# Microcontroller.net
KiCad netlist of a schematic drawn in Altium Designer
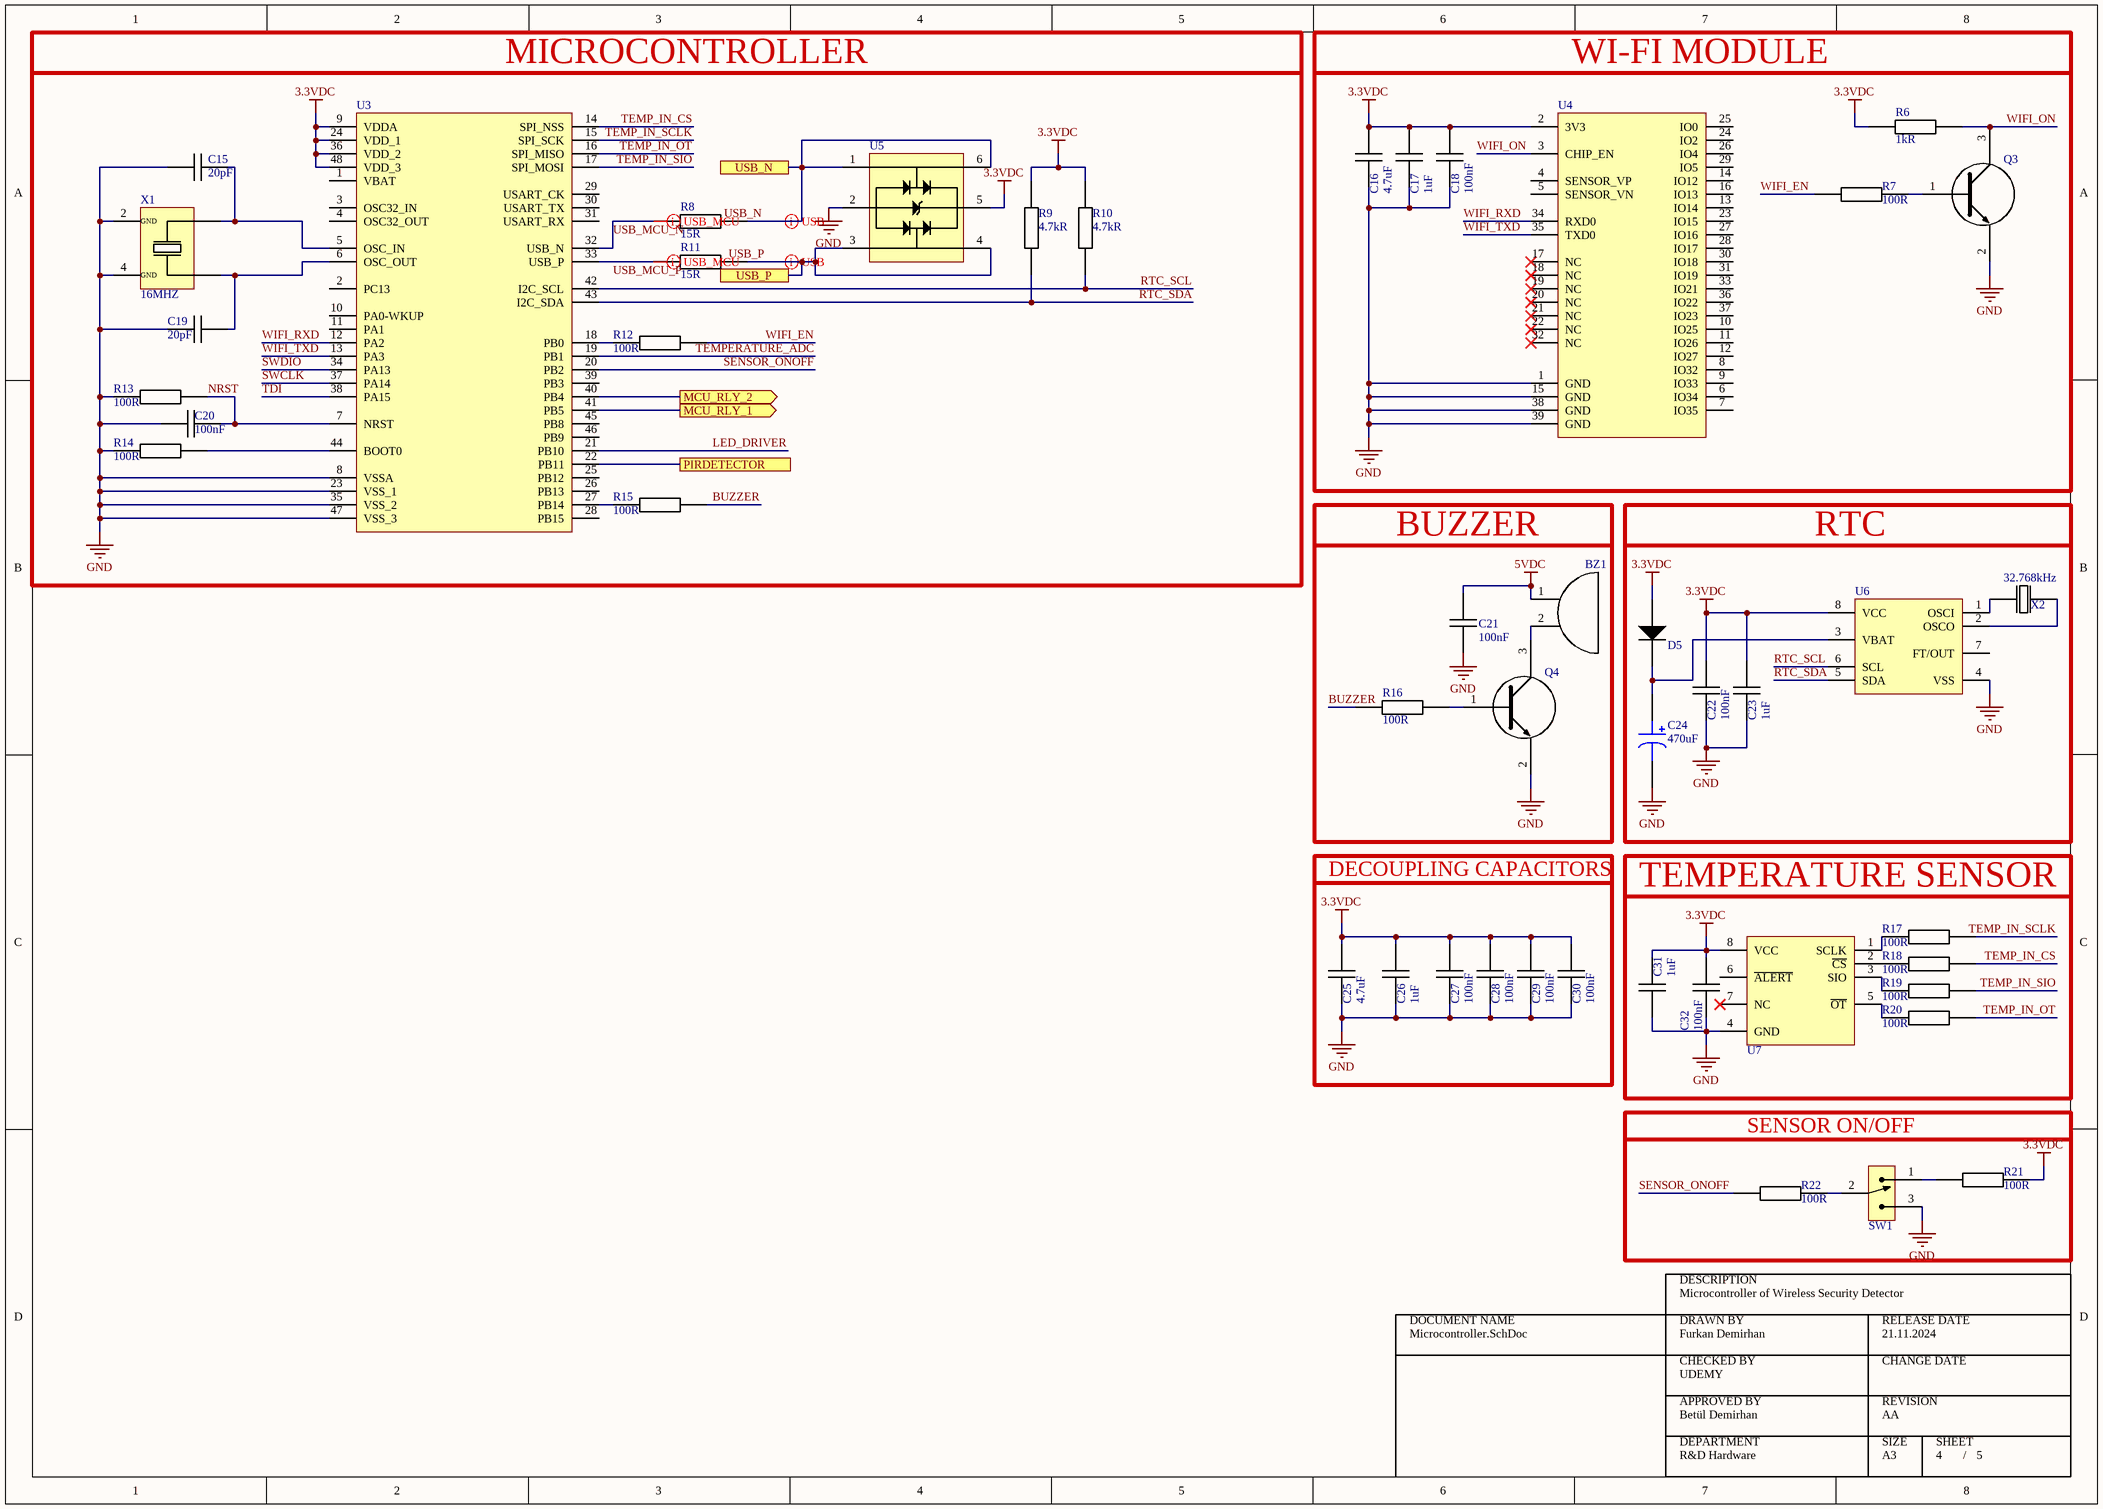
[diagram p0: Microcontroller.SchDoc]

(export (version "E")
  (design (tool "Eeschema 10.0.6"))
  (components
    (comp (ref "BZ1")
      (value "CMI-9605IC-0580T")
      (footprint "CMI-9605IC-0580T")
      (description "Audio Buzzer Magnetic 3VDC 7VDC 30mA 5VDC 85dB 2600Hz to 2800Hz Through Hole Pin Box")
      (fields (field (name "MANUFACTURER") "CUI Devices") (field (name "DESIGNED BY") "FURKAN"))
      (libsource (lib "Udemy_Library") (part "CMI-9605IC-0580T"))
    )
    (comp (ref "C15")
      (value "20pF")
      (footprint "CAP_0603")
      (description "CAP CER 20pF ±5% 0603 SMD")
      (fields
        (field (name "MANUFACTURER") "Samsung")
        (field (name "MANUFACTURER PART NUMBER") "CL10C200JB8NNNC")
        (field (name "DESIGNED BY") "FURKAN")
      )
      (libsource (lib "Udemy_Library") (part "CAP CER 20pF 0603"))
    )
    (comp (ref "C16")
      (value "4.7uF")
      (footprint "CAP_0805")
      (description "Multilayer Ceramic Capacitor, 4.7 uF, 25 V, ± 10%, X5R, 0805 [2012 Metric]")
      (fields
        (field (name "MANUFACTURER") "Samsung")
        (field (name "MANUFACTURER PART NUMBER") "CL21A475KAQNNNE")
        (field (name "DESIGNED BY") "FURKAN")
      )
      (libsource (lib "Udemy_Library") (part "CAP CER 4.7uF 0805"))
    )
    (comp (ref "C17")
      (value "1uF")
      (footprint "CAP_0805")
      (description "Multilayer Ceramic Capacitor, 1 uF, 50 V, 10%, X7R, 0805 [2012 Metric]")
      (fields
        (field (name "MANUFACTURER") "Samsung")
        (field (name "MANUFACTURER PART NUMBER") "CL21B105KBFNNNE")
        (field (name "DESIGNED BY") "FURKAN")
      )
      (libsource (lib "Udemy_Library") (part "CAP CER 1uF 0805"))
    )
    (comp (ref "C18")
      (value "100nF")
      (footprint "CAP_0805")
      (description "CAP CER 100 nF 10% 50 V 0805 SMD")
      (fields
        (field (name "MANUFACTURER") "Samsung")
        (field (name "MANUFACTURER PART NUMBER") "CL21B104KBCNNNC")
        (field (name "DESIGNED BY") "FURKAN")
      )
      (libsource (lib "Udemy_Library") (part "CAP CER 100nF 0805"))
    )
    (comp (ref "C19")
      (value "20pF")
      (footprint "CAP_0603")
      (description "CAP CER 20pF ±5% 0603 SMD")
      (fields
        (field (name "MANUFACTURER") "Samsung")
        (field (name "MANUFACTURER PART NUMBER") "CL10C200JB8NNNC")
        (field (name "DESIGNED BY") "FURKAN")
      )
      (libsource (lib "Udemy_Library") (part "CAP CER 20pF 0603"))
    )
    (comp (ref "C20")
      (value "100nF")
      (footprint "CAP_0805")
      (description "CAP CER 100 nF 10% 50 V 0805 SMD")
      (fields
        (field (name "MANUFACTURER") "Samsung")
        (field (name "MANUFACTURER PART NUMBER") "CL21B104KBCNNNC")
        (field (name "DESIGNED BY") "FURKAN")
      )
      (libsource (lib "Udemy_Library") (part "CAP CER 100nF 0805"))
    )
    (comp (ref "C21")
      (value "100nF")
      (footprint "CAP_0805")
      (description "CAP CER 100 nF 10% 50 V 0805 SMD")
      (fields
        (field (name "MANUFACTURER") "Samsung")
        (field (name "MANUFACTURER PART NUMBER") "CL21B104KBCNNNC")
        (field (name "DESIGNED BY") "FURKAN")
      )
      (libsource (lib "Udemy_Library") (part "CAP CER 100nF 0805"))
    )
    (comp (ref "C22")
      (value "100nF")
      (footprint "CAP_0805")
      (description "CAP CER 100 nF 10% 50 V 0805 SMD")
      (fields
        (field (name "MANUFACTURER") "Samsung")
        (field (name "MANUFACTURER PART NUMBER") "CL21B104KBCNNNC")
        (field (name "DESIGNED BY") "FURKAN")
      )
      (libsource (lib "Udemy_Library") (part "CAP CER 100nF 0805"))
    )
    (comp (ref "C23")
      (value "1uF")
      (footprint "CAP_0805")
      (description "Multilayer Ceramic Capacitor, 1 uF, 50 V, 10%, X7R, 0805 [2012 Metric]")
      (fields
        (field (name "MANUFACTURER") "Samsung")
        (field (name "MANUFACTURER PART NUMBER") "CL21B105KBFNNNE")
        (field (name "DESIGNED BY") "FURKAN")
      )
      (libsource (lib "Udemy_Library") (part "CAP CER 1uF 0805"))
    )
    (comp (ref "C24")
      (value "ESH477M050AH4AA")
      (footprint "CAP_RADIAL_R10_P5")
      (description "Electrolytic capacitor, 470 µF, 50 V (DC), ±20 %, radial, pitch 5 mm, Ø 13 mm")
      (fields
        (field (name "MANUFACTURER") "KEMET")
        (field (name "CAPACITANCE") "470uF")
        (field (name "DESIGNED BY") "FURKAN")
      )
      (libsource (lib "Udemy_Library") (part "CAP ALU ELEC 470uF"))
    )
    (comp (ref "C25")
      (value "4.7uF")
      (footprint "CAP_0805")
      (description "Multilayer Ceramic Capacitor, 4.7 uF, 25 V, ± 10%, X5R, 0805 [2012 Metric]")
      (fields
        (field (name "MANUFACTURER") "Samsung")
        (field (name "MANUFACTURER PART NUMBER") "CL21A475KAQNNNE")
        (field (name "DESIGNED BY") "FURKAN")
      )
      (libsource (lib "Udemy_Library") (part "CAP CER 4.7uF 0805"))
    )
    (comp (ref "C26")
      (value "1uF")
      (footprint "CAP_0805")
      (description "Multilayer Ceramic Capacitor, 1 uF, 50 V, 10%, X7R, 0805 [2012 Metric]")
      (fields
        (field (name "MANUFACTURER") "Samsung")
        (field (name "MANUFACTURER PART NUMBER") "CL21B105KBFNNNE")
        (field (name "DESIGNED BY") "FURKAN")
      )
      (libsource (lib "Udemy_Library") (part "CAP CER 1uF 0805"))
    )
    (comp (ref "C27")
      (value "100nF")
      (footprint "CAP_0805")
      (description "CAP CER 100 nF 10% 50 V 0805 SMD")
      (fields
        (field (name "MANUFACTURER") "Samsung")
        (field (name "MANUFACTURER PART NUMBER") "CL21B104KBCNNNC")
        (field (name "DESIGNED BY") "FURKAN")
      )
      (libsource (lib "Udemy_Library") (part "CAP CER 100nF 0805"))
    )
    (comp (ref "C28")
      (value "100nF")
      (footprint "CAP_0805")
      (description "CAP CER 100 nF 10% 50 V 0805 SMD")
      (fields
        (field (name "MANUFACTURER") "Samsung")
        (field (name "MANUFACTURER PART NUMBER") "CL21B104KBCNNNC")
        (field (name "DESIGNED BY") "FURKAN")
      )
      (libsource (lib "Udemy_Library") (part "CAP CER 100nF 0805"))
    )
    (comp (ref "C29")
      (value "100nF")
      (footprint "CAP_0805")
      (description "CAP CER 100 nF 10% 50 V 0805 SMD")
      (fields
        (field (name "MANUFACTURER") "Samsung")
        (field (name "MANUFACTURER PART NUMBER") "CL21B104KBCNNNC")
        (field (name "DESIGNED BY") "FURKAN")
      )
      (libsource (lib "Udemy_Library") (part "CAP CER 100nF 0805"))
    )
    (comp (ref "C30")
      (value "100nF")
      (footprint "CAP_0805")
      (description "CAP CER 100 nF 10% 50 V 0805 SMD")
      (fields
        (field (name "MANUFACTURER") "Samsung")
        (field (name "MANUFACTURER PART NUMBER") "CL21B104KBCNNNC")
        (field (name "DESIGNED BY") "FURKAN")
      )
      (libsource (lib "Udemy_Library") (part "CAP CER 100nF 0805"))
    )
    (comp (ref "C31")
      (value "1uF")
      (footprint "CAP_0805")
      (description "Multilayer Ceramic Capacitor, 1 uF, 50 V, 10%, X7R, 0805 [2012 Metric]")
      (fields
        (field (name "MANUFACTURER") "Samsung")
        (field (name "MANUFACTURER PART NUMBER") "CL21B105KBFNNNE")
        (field (name "DESIGNED BY") "FURKAN")
      )
      (libsource (lib "Udemy_Library") (part "CAP CER 1uF 0805"))
    )
    (comp (ref "C32")
      (value "100nF")
      (footprint "CAP_0805")
      (description "CAP CER 100 nF 10% 50 V 0805 SMD")
      (fields
        (field (name "MANUFACTURER") "Samsung")
        (field (name "MANUFACTURER PART NUMBER") "CL21B104KBCNNNC")
        (field (name "DESIGNED BY") "FURKAN")
      )
      (libsource (lib "Udemy_Library") (part "CAP CER 100nF 0805"))
    )
    (comp (ref "D5")
      (value "1N4148WS")
      (footprint "SOD323F")
      (description "Diode Ultra Fast Recovery Rectifier 75V 0.15A 2-Pin SOD-323F T/R")
      (fields
        (field (name "MANUFACTURER") "ON Semiconductor / Fairchild")
        (field (name "DESIGNED BY") "FURKAN")
      )
      (libsource (lib "Udemy_Library") (part "1N4148WS"))
    )
    (comp (ref "Q3")
      (value "MMBT3904-7-F")
      (footprint "SOT23F")
      (description "Transistor General Purpose BJT NPN 40 Volt 0.2A Automotive 3-Pin SOT-23")
      (fields (field (name "MANUFACTURER") "Diodes Zetex") (field (name "DESIGNED BY") "FURKAN"))
      (libsource (lib "Udemy_Library") (part "MMBT3904-7-F"))
    )
    (comp (ref "Q4")
      (value "MMBT3904-7-F")
      (footprint "SOT23F")
      (description "Transistor General Purpose BJT NPN 40 Volt 0.2A Automotive 3-Pin SOT-23")
      (fields (field (name "MANUFACTURER") "Diodes Zetex") (field (name "DESIGNED BY") "FURKAN"))
      (libsource (lib "Udemy_Library") (part "MMBT3904-7-F"))
    )
    (comp (ref "R6")
      (value "1kR")
      (footprint "RES_0603")
      (description "RES 1K OHM 1% 0603 SMD")
      (fields
        (field (name "MANUFACTURER") "Yageo")
        (field (name "MANUFACTURER PART NUMBER") "RC0603FR-071KL")
        (field (name "DESIGNED BY") "FURKAN")
      )
      (libsource (lib "Udemy_Library") (part "RES 1K OHM 0603"))
    )
    (comp (ref "R7")
      (value "100R")
      (footprint "RES_0603")
      (description "RES 100 OHM 1% 0603 SMD")
      (fields
        (field (name "MANUFACTURER") "Yageo")
        (field (name "MANUFACTURER PART NUMBER") "RC0603FR-07100RL")
        (field (name "DESIGNED BY") "FURKAN")
      )
      (libsource (lib "Udemy_Library") (part "RES 100 OHM 0603"))
    )
    (comp (ref "R8")
      (value "15R")
      (footprint "RES_0603")
      (description "RES 15 OHM 5% 0603 SMD")
      (fields
        (field (name "MANUFACTURER") "Yageo")
        (field (name "MANUFACTURER PART NUMBER") "RC0603JR-0715RL")
        (field (name "DESIGNED BY") "FURKAN")
      )
      (libsource (lib "Udemy_Library") (part "RES 15 OHM 0603"))
    )
    (comp (ref "R9")
      (value "4.7kR")
      (footprint "RES_0603")
      (description "RES 4.7K OHM 5% 0603 SMD")
      (fields
        (field (name "MANUFACTURER") "Yageo")
        (field (name "MANUFACTURER PART NUMBER") "RC0603JR-074K7L")
        (field (name "DESIGNED BY") "FURKAN")
      )
      (libsource (lib "Udemy_Library") (part "RES 4.7K OHM 0603"))
    )
    (comp (ref "R10")
      (value "4.7kR")
      (footprint "RES_0603")
      (description "RES 4.7K OHM 5% 0603 SMD")
      (fields
        (field (name "MANUFACTURER") "Yageo")
        (field (name "MANUFACTURER PART NUMBER") "RC0603JR-074K7L")
        (field (name "DESIGNED BY") "FURKAN")
      )
      (libsource (lib "Udemy_Library") (part "RES 4.7K OHM 0603"))
    )
    (comp (ref "R11")
      (value "15R")
      (footprint "RES_0603")
      (description "RES 15 OHM 5% 0603 SMD")
      (fields
        (field (name "MANUFACTURER") "Yageo")
        (field (name "MANUFACTURER PART NUMBER") "RC0603JR-0715RL")
        (field (name "DESIGNED BY") "FURKAN")
      )
      (libsource (lib "Udemy_Library") (part "RES 15 OHM 0603"))
    )
    (comp (ref "R12")
      (value "100R")
      (footprint "RES_0603")
      (description "RES 100 OHM 1% 0603 SMD")
      (fields
        (field (name "MANUFACTURER") "Yageo")
        (field (name "MANUFACTURER PART NUMBER") "RC0603FR-07100RL")
        (field (name "DESIGNED BY") "FURKAN")
      )
      (libsource (lib "Udemy_Library") (part "RES 100 OHM 0603"))
    )
    (comp (ref "R13")
      (value "100R")
      (footprint "RES_0603")
      (description "RES 100 OHM 1% 0603 SMD")
      (fields
        (field (name "MANUFACTURER") "Yageo")
        (field (name "MANUFACTURER PART NUMBER") "RC0603FR-07100RL")
        (field (name "DESIGNED BY") "FURKAN")
      )
      (libsource (lib "Udemy_Library") (part "RES 100 OHM 0603"))
    )
    (comp (ref "R14")
      (value "100R")
      (footprint "RES_0603")
      (description "RES 100 OHM 1% 0603 SMD")
      (fields
        (field (name "MANUFACTURER") "Yageo")
        (field (name "MANUFACTURER PART NUMBER") "RC0603FR-07100RL")
        (field (name "DESIGNED BY") "FURKAN")
      )
      (libsource (lib "Udemy_Library") (part "RES 100 OHM 0603"))
    )
    (comp (ref "R15")
      (value "100R")
      (footprint "RES_0603")
      (description "RES 100 OHM 1% 0603 SMD")
      (fields
        (field (name "MANUFACTURER") "Yageo")
        (field (name "MANUFACTURER PART NUMBER") "RC0603FR-07100RL")
        (field (name "DESIGNED BY") "FURKAN")
      )
      (libsource (lib "Udemy_Library") (part "RES 100 OHM 0603"))
    )
    (comp (ref "R16")
      (value "100R")
      (footprint "RES_0603")
      (description "RES 100 OHM 1% 0603 SMD")
      (fields
        (field (name "MANUFACTURER") "Yageo")
        (field (name "MANUFACTURER PART NUMBER") "RC0603FR-07100RL")
        (field (name "DESIGNED BY") "FURKAN")
      )
      (libsource (lib "Udemy_Library") (part "RES 100 OHM 0603"))
    )
    (comp (ref "R17")
      (value "100R")
      (footprint "RES_0603")
      (description "RES 100 OHM 1% 0603 SMD")
      (fields
        (field (name "MANUFACTURER") "Yageo")
        (field (name "MANUFACTURER PART NUMBER") "RC0603FR-07100RL")
        (field (name "DESIGNED BY") "FURKAN")
      )
      (libsource (lib "Udemy_Library") (part "RES 100 OHM 0603"))
    )
    (comp (ref "R18")
      (value "100R")
      (footprint "RES_0603")
      (description "RES 100 OHM 1% 0603 SMD")
      (fields
        (field (name "MANUFACTURER") "Yageo")
        (field (name "MANUFACTURER PART NUMBER") "RC0603FR-07100RL")
        (field (name "DESIGNED BY") "FURKAN")
      )
      (libsource (lib "Udemy_Library") (part "RES 100 OHM 0603"))
    )
    (comp (ref "R19")
      (value "100R")
      (footprint "RES_0603")
      (description "RES 100 OHM 1% 0603 SMD")
      (fields
        (field (name "MANUFACTURER") "Yageo")
        (field (name "MANUFACTURER PART NUMBER") "RC0603FR-07100RL")
        (field (name "DESIGNED BY") "FURKAN")
      )
      (libsource (lib "Udemy_Library") (part "RES 100 OHM 0603"))
    )
    (comp (ref "R20")
      (value "100R")
      (footprint "RES_0603")
      (description "RES 100 OHM 1% 0603 SMD")
      (fields
        (field (name "MANUFACTURER") "Yageo")
        (field (name "MANUFACTURER PART NUMBER") "RC0603FR-07100RL")
        (field (name "DESIGNED BY") "FURKAN")
      )
      (libsource (lib "Udemy_Library") (part "RES 100 OHM 0603"))
    )
    (comp (ref "R21")
      (value "100R")
      (footprint "RES_0603")
      (description "RES 100 OHM 1% 0603 SMD")
      (fields
        (field (name "MANUFACTURER") "Yageo")
        (field (name "MANUFACTURER PART NUMBER") "RC0603FR-07100RL")
        (field (name "DESIGNED BY") "FURKAN")
      )
      (libsource (lib "Udemy_Library") (part "RES 100 OHM 0603"))
    )
    (comp (ref "R22")
      (value "100R")
      (footprint "RES_0603")
      (description "RES 100 OHM 1% 0603 SMD")
      (fields
        (field (name "MANUFACTURER") "Yageo")
        (field (name "MANUFACTURER PART NUMBER") "RC0603FR-07100RL")
        (field (name "DESIGNED BY") "FURKAN")
      )
      (libsource (lib "Udemy_Library") (part "RES 100 OHM 0603"))
    )
    (comp (ref "SW1")
      (value "EG1215AA")
      (footprint "EG1215AA")
      (description "Slide Switch, SPDT, 0.025A, 24V, SMD")
      (fields (field (name "MANUFACTURER") "E-Switch") (field (name "DESIGNED BY") "FURKAN"))
      (libsource (lib "Udemy_Library") (part "EG1215AA"))
    )
    (comp (ref "U3")
      (value "STM32F103C6T6A")
      (footprint "LQFP48")
      (description "MCU 32-bit STM32F ARM Cortex M3 RISC 32KB Flash 2.5V/3.3V 48-Pin LQFP Tray")
      (fields (field (name "MANUFACTURER") "STMicroelectronics") (field (name "DESIGNED BY") "FURKAN"))
      (libsource (lib "Udemy_Library") (part "STM32F103C6T6A"))
    )
    (comp (ref "U4")
      (value "ESP32-WROOM-32E-N4")
      (footprint "ESP32-WROOM-32E-N4")
      (description "SMD module, ESP32-D0WD-V3, ESP32 ECO V3, 4 MB SPI flash, PCB antenna")
      (fields
        (field (name "MANUFACTURER") "Espressif Systems")
        (field (name "MANUFACTURER PART NUMBER") "ESP32-WROOM-32E(M113EH3200PH3Q0)")
        (field (name "DESIGNED BY") "FURKAN")
      )
      (libsource (lib "Udemy_Library") (part "ESP32-WROOM-32E-N4"))
    )
    (comp (ref "U5")
      (value "USBLC6-2SC6")
      (footprint "SOT23-6L")
      (description "ESD Suppressor Diode Array Dual Uni-Dir 15kV Air Gap/15kV Contact Disc 6-Pin SOT-23 T/R")
      (fields (field (name "MANUFACTURER") "STMicroelectronics") (field (name "DESIGNED BY") "FURKAN"))
      (libsource (lib "Udemy_Library") (part "USB PROTECTION"))
    )
    (comp (ref "U6")
      (value "M41T00M6F")
      (footprint "SOIC8")
      (description "M41T00 Series 5.5 V I2C / 2-Wire / Serial Surface Mount Real Time Clock - SOIC-8")
      (fields (field (name "MANUFACTURER") "STMicroelectronics") (field (name "DESIGNED BY") "FURKAN"))
      (libsource (lib "Udemy_Library") (part "M41T00M6F"))
    )
    (comp (ref "U7")
      (value "MAX6662MSA+")
      (footprint "SOIC8")
      (description "Temp Sensor Digital Serial (3-Wire, SPI) 8-Pin SOIC N Tube")
      (fields (field (name "MANUFACTURER") "Maxim") (field (name "DESIGNED BY") "FURKAN"))
      (libsource (lib "Udemy_Library") (part "MAX6662MSA+"))
    )
    (comp (ref "X1")
      (value "ECS-160-20-30B-TR")
      (footprint "ECS")
      (description "Crystal 16MHz ±30ppm (Tol) ±50ppm (Stability) 20pF FUND 50Ohm 4-Pin Mini-SMD T/R")
      (fields
        (field (name "MANUFACTURER") "ECS International")
        (field (name "FREQUENCY") "16MHZ")
        (field (name "DESIGNED BY") "FURKAN")
      )
      (libsource (lib "Udemy_Library") (part "CRYSTAL 16MHZ"))
    )
    (comp (ref "X2")
      (value "ABS05-32.768KHZ-T")
      (footprint "ABS05")
      (description "Crystal 32.768kHz ±20ppm (Tol) 12.5pF Flexural 90000Ohm 2-Pin CSMD T/R")
      (fields
        (field (name "MANUFACTURER") "Abracon")
        (field (name "TOLERANCE") "20ppm")
        (field (name "FREQUENCY") "32.768kHz")
        (field (name "DESIGNED BY") "FURKAN")
      )
      (libsource (lib "Udemy_Library") (part "CRYSTAL 32.768kHZ"))
    )
  )
  (nets
    (net (code "1") (name "/BUZZER") (class "Default")
      (node (ref "R15") (pin "2") (pinfunction "2_2") (pintype "passive"))
      (node (ref "R16") (pin "1") (pinfunction "1_1") (pintype "passive"))
    )
    (net (code "2") (name "/LED_DRIVER") (class "Default")
      (node (ref "U3") (pin "21") (pinfunction "PB10_21") (pintype "passive"))
    )
    (net (code "3") (name "/MCU_RLY_1") (class "Default")
      (node (ref "U3") (pin "41") (pinfunction "PB5_41") (pintype "passive"))
    )
    (net (code "4") (name "/MCU_RLY_2") (class "Default")
      (node (ref "U3") (pin "40") (pinfunction "PB4_40") (pintype "passive"))
    )
    (net (code "5") (name "/NRST") (class "Default")
      (node (ref "C20") (pin "1") (pinfunction "1_1") (pintype "passive"))
      (node (ref "R13") (pin "2") (pinfunction "2_2") (pintype "passive"))
      (node (ref "U3") (pin "7") (pinfunction "NRST_7") (pintype "passive"))
    )
    (net (code "6") (name "/PIRDETECTOR") (class "Default")
      (node (ref "U3") (pin "22") (pinfunction "PB11_22") (pintype "passive"))
    )
    (net (code "7") (name "/RTC_SCL") (class "Default")
      (node (ref "R10") (pin "1") (pinfunction "1_1") (pintype "passive"))
      (node (ref "U3") (pin "42") (pinfunction "I2C_SCL_42") (pintype "passive"))
      (node (ref "U6") (pin "6") (pinfunction "SCL_6") (pintype "passive"))
    )
    (net (code "8") (name "/RTC_SDA") (class "Default")
      (node (ref "R9") (pin "1") (pinfunction "1_1") (pintype "passive"))
      (node (ref "U3") (pin "43") (pinfunction "I2C_SDA_43") (pintype "passive"))
      (node (ref "U6") (pin "5") (pinfunction "SDA_5") (pintype "passive"))
    )
    (net (code "9") (name "/SENSOR_ONOFF") (class "Default")
      (node (ref "R22") (pin "1") (pinfunction "1_1") (pintype "passive"))
      (node (ref "U3") (pin "20") (pinfunction "PB2_20") (pintype "passive"))
    )
    (net (code "10") (name "/SWCLK") (class "Default")
      (node (ref "U3") (pin "37") (pinfunction "PA14_37") (pintype "passive"))
    )
    (net (code "11") (name "/SWDIO") (class "Default")
      (node (ref "U3") (pin "34") (pinfunction "PA13_34") (pintype "passive"))
    )
    (net (code "12") (name "/TDI") (class "Default")
      (node (ref "U3") (pin "38") (pinfunction "PA15_38") (pintype "passive"))
    )
    (net (code "13") (name "/TEMPERATURE_ADC") (class "Default")
      (node (ref "U3") (pin "19") (pinfunction "PB1_19") (pintype "passive"))
    )
    (net (code "14") (name "/TEMP_IN_CS") (class "Default")
      (node (ref "R18") (pin "2") (pinfunction "2_2") (pintype "passive"))
      (node (ref "U3") (pin "14") (pinfunction "SPI_NSS_14") (pintype "passive"))
    )
    (net (code "15") (name "/TEMP_IN_OT") (class "Default")
      (node (ref "R20") (pin "2") (pinfunction "2_2") (pintype "passive"))
      (node (ref "U3") (pin "16") (pinfunction "SPI_MISO_16") (pintype "passive"))
    )
    (net (code "16") (name "/TEMP_IN_SCLK") (class "Default")
      (node (ref "R17") (pin "2") (pinfunction "2_2") (pintype "passive"))
      (node (ref "U3") (pin "15") (pinfunction "SPI_SCK_15") (pintype "passive"))
    )
    (net (code "17") (name "/TEMP_IN_SIO") (class "Default")
      (node (ref "R19") (pin "2") (pinfunction "2_2") (pintype "passive"))
      (node (ref "U3") (pin "17") (pinfunction "SPI_MOSI_17") (pintype "passive"))
    )
    (net (code "18") (name "/USB_MCU_N") (class "Default")
      (node (ref "R8") (pin "1") (pinfunction "1_1") (pintype "passive"))
      (node (ref "U3") (pin "32") (pinfunction "USB_N_32") (pintype "passive"))
    )
    (net (code "19") (name "/USB_MCU_P") (class "Default")
      (node (ref "R11") (pin "1") (pinfunction "1_1") (pintype "passive"))
      (node (ref "U3") (pin "33") (pinfunction "USB_P_33") (pintype "passive"))
    )
    (net (code "20") (name "/USB_N") (class "Default")
      (node (ref "R8") (pin "2") (pinfunction "2_2") (pintype "passive"))
      (node (ref "U5") (pin "1") (pinfunction "I/O1_1") (pintype "passive"))
      (node (ref "U5") (pin "6") (pinfunction "I/O1_6") (pintype "passive"))
    )
    (net (code "21") (name "/USB_P") (class "Default")
      (node (ref "R11") (pin "2") (pinfunction "2_2") (pintype "passive"))
      (node (ref "U5") (pin "3") (pinfunction "I/O2_3") (pintype "passive"))
      (node (ref "U5") (pin "4") (pinfunction "I/O2_4") (pintype "passive"))
    )
    (net (code "22") (name "/WIFI_EN") (class "Default")
      (node (ref "R12") (pin "2") (pinfunction "2_2") (pintype "passive"))
      (node (ref "R7") (pin "1") (pinfunction "1_1") (pintype "passive"))
    )
    (net (code "23") (name "/WIFI_ON") (class "Default")
      (node (ref "Q3") (pin "3") (pinfunction "C_3") (pintype "passive"))
      (node (ref "R6") (pin "2") (pinfunction "2_2") (pintype "passive"))
      (node (ref "U4") (pin "3") (pinfunction "CHIP_EN_3") (pintype "passive"))
    )
    (net (code "24") (name "/WIFI_RXD") (class "Default")
      (node (ref "U3") (pin "12") (pinfunction "PA2_12") (pintype "passive"))
      (node (ref "U4") (pin "34") (pinfunction "RXD0_34") (pintype "passive"))
    )
    (net (code "25") (name "/WIFI_TXD") (class "Default")
      (node (ref "U3") (pin "13") (pinfunction "PA3_13") (pintype "passive"))
      (node (ref "U4") (pin "35") (pinfunction "TXD0_35") (pintype "passive"))
    )
    (net (code "26") (name "3.3VDC") (class "Default")
      (node (ref "C16") (pin "1") (pinfunction "1_1") (pintype "passive"))
      (node (ref "C17") (pin "1") (pinfunction "1_1") (pintype "passive"))
      (node (ref "C18") (pin "1") (pinfunction "1_1") (pintype "passive"))
      (node (ref "C22") (pin "2") (pinfunction "2_2") (pintype "passive"))
      (node (ref "C23") (pin "2") (pinfunction "2_2") (pintype "passive"))
      (node (ref "C25") (pin "2") (pinfunction "2_2") (pintype "passive"))
      (node (ref "C26") (pin "2") (pinfunction "2_2") (pintype "passive"))
      (node (ref "C27") (pin "2") (pinfunction "2_2") (pintype "passive"))
      (node (ref "C28") (pin "2") (pinfunction "2_2") (pintype "passive"))
      (node (ref "C29") (pin "2") (pinfunction "2_2") (pintype "passive"))
      (node (ref "C30") (pin "2") (pinfunction "2_2") (pintype "passive"))
      (node (ref "C31") (pin "2") (pinfunction "2_2") (pintype "passive"))
      (node (ref "C32") (pin "2") (pinfunction "2_2") (pintype "passive"))
      (node (ref "D5") (pin "2") (pinfunction "2_2") (pintype "passive"))
      (node (ref "R10") (pin "2") (pinfunction "2_2") (pintype "passive"))
      (node (ref "R21") (pin "2") (pinfunction "2_2") (pintype "passive"))
      (node (ref "R6") (pin "1") (pinfunction "1_1") (pintype "passive"))
      (node (ref "R9") (pin "2") (pinfunction "2_2") (pintype "passive"))
      (node (ref "U3") (pin "24") (pinfunction "VDD_1_24") (pintype "passive"))
      (node (ref "U3") (pin "36") (pinfunction "VDD_2_36") (pintype "passive"))
      (node (ref "U3") (pin "48") (pinfunction "VDD_3_48") (pintype "passive"))
      (node (ref "U3") (pin "9") (pinfunction "VDDA_9") (pintype "passive"))
      (node (ref "U4") (pin "2") (pinfunction "3V3_2") (pintype "passive"))
      (node (ref "U5") (pin "5") (pinfunction "VBUS_5") (pintype "passive"))
      (node (ref "U6") (pin "8") (pinfunction "VCC_8") (pintype "passive"))
      (node (ref "U7") (pin "8") (pinfunction "VCC_8") (pintype "passive"))
    )
    (net (code "27") (name "5VDC") (class "Default")
      (node (ref "BZ1") (pin "1") (pinfunction "1_1") (pintype "passive"))
      (node (ref "C21") (pin "2") (pinfunction "2_2") (pintype "passive"))
    )
    (net (code "28") (name "GND") (class "Default")
      (node (ref "C15") (pin "1") (pinfunction "1_1") (pintype "passive"))
      (node (ref "C16") (pin "2") (pinfunction "2_2") (pintype "passive"))
      (node (ref "C17") (pin "2") (pinfunction "2_2") (pintype "passive"))
      (node (ref "C18") (pin "2") (pinfunction "2_2") (pintype "passive"))
      (node (ref "C19") (pin "1") (pinfunction "1_1") (pintype "passive"))
      (node (ref "C20") (pin "2") (pinfunction "2_2") (pintype "passive"))
      (node (ref "C21") (pin "1") (pinfunction "1_1") (pintype "passive"))
      (node (ref "C22") (pin "1") (pinfunction "1_1") (pintype "passive"))
      (node (ref "C23") (pin "1") (pinfunction "1_1") (pintype "passive"))
      (node (ref "C24") (pin "2") (pinfunction "2_2") (pintype "passive"))
      (node (ref "C25") (pin "1") (pinfunction "1_1") (pintype "passive"))
      (node (ref "C26") (pin "1") (pinfunction "1_1") (pintype "passive"))
      (node (ref "C27") (pin "1") (pinfunction "1_1") (pintype "passive"))
      (node (ref "C28") (pin "1") (pinfunction "1_1") (pintype "passive"))
      (node (ref "C29") (pin "1") (pinfunction "1_1") (pintype "passive"))
      (node (ref "C30") (pin "1") (pinfunction "1_1") (pintype "passive"))
      (node (ref "C31") (pin "1") (pinfunction "1_1") (pintype "passive"))
      (node (ref "C32") (pin "1") (pinfunction "1_1") (pintype "passive"))
      (node (ref "Q3") (pin "2") (pinfunction "E_2") (pintype "passive"))
      (node (ref "Q4") (pin "2") (pinfunction "E_2") (pintype "passive"))
      (node (ref "R13") (pin "1") (pinfunction "1_1") (pintype "passive"))
      (node (ref "R14") (pin "1") (pinfunction "1_1") (pintype "passive"))
      (node (ref "SW1") (pin "3") (pinfunction "3_3") (pintype "passive"))
      (node (ref "U3") (pin "23") (pinfunction "VSS_1_23") (pintype "passive"))
      (node (ref "U3") (pin "35") (pinfunction "VSS_2_35") (pintype "passive"))
      (node (ref "U3") (pin "47") (pinfunction "VSS_3_47") (pintype "passive"))
      (node (ref "U3") (pin "8") (pinfunction "VSSA_8") (pintype "passive"))
      (node (ref "U4") (pin "1") (pinfunction "GND_1") (pintype "passive"))
      (node (ref "U4") (pin "15") (pinfunction "GND_15") (pintype "passive"))
      (node (ref "U4") (pin "38") (pinfunction "GND_38") (pintype "passive"))
      (node (ref "U4") (pin "39") (pinfunction "GND_39") (pintype "passive"))
      (node (ref "U5") (pin "2") (pinfunction "GND_2") (pintype "passive"))
      (node (ref "U6") (pin "4") (pinfunction "VSS_4") (pintype "passive"))
      (node (ref "U7") (pin "4") (pinfunction "GND_4") (pintype "passive"))
      (node (ref "X1") (pin "2") (pinfunction "GND_2") (pintype "passive"))
      (node (ref "X1") (pin "4") (pinfunction "GND_4") (pintype "passive"))
    )
    (net (code "29") (name "Net-(Q3-B)") (class "Default")
      (node (ref "Q3") (pin "1") (pinfunction "B_1") (pintype "passive"))
      (node (ref "R7") (pin "2") (pinfunction "2_2") (pintype "passive"))
    )
    (net (code "30") (name "Net-(Q4-B)") (class "Default")
      (node (ref "Q4") (pin "1") (pinfunction "B_1") (pintype "passive"))
      (node (ref "R16") (pin "2") (pinfunction "2_2") (pintype "passive"))
    )
    (net (code "31") (name "Net-(Q4-C)") (class "Default")
      (node (ref "BZ1") (pin "2") (pinfunction "2_2") (pintype "passive"))
      (node (ref "Q4") (pin "3") (pinfunction "C_3") (pintype "passive"))
    )
    (net (code "32") (name "Net-(R21-Pad1)") (class "Default")
      (node (ref "R21") (pin "1") (pinfunction "1_1") (pintype "passive"))
      (node (ref "SW1") (pin "1") (pinfunction "1_1") (pintype "passive"))
    )
    (net (code "33") (name "Net-(R22-Pad2)") (class "Default")
      (node (ref "R22") (pin "2") (pinfunction "2_2") (pintype "passive"))
      (node (ref "SW1") (pin "2") (pinfunction "2_2") (pintype "passive"))
    )
    (net (code "34") (name "Net-(U3-BOOT0)") (class "Default")
      (node (ref "R14") (pin "2") (pinfunction "2_2") (pintype "passive"))
      (node (ref "U3") (pin "44") (pinfunction "BOOT0_44") (pintype "passive"))
    )
    (net (code "35") (name "Net-(U3-OSC_IN)") (class "Default")
      (node (ref "C15") (pin "2") (pinfunction "2_2") (pintype "passive"))
      (node (ref "U3") (pin "5") (pinfunction "OSC_IN_5") (pintype "passive"))
      (node (ref "X1") (pin "1") (pinfunction "1_1") (pintype "passive"))
    )
    (net (code "36") (name "Net-(U3-OSC_OUT)") (class "Default")
      (node (ref "C19") (pin "2") (pinfunction "2_2") (pintype "passive"))
      (node (ref "U3") (pin "6") (pinfunction "OSC_OUT_6") (pintype "passive"))
      (node (ref "X1") (pin "3") (pinfunction "3_3") (pintype "passive"))
    )
    (net (code "37") (name "Net-(U3-PB0)") (class "Default")
      (node (ref "R12") (pin "1") (pinfunction "1_1") (pintype "passive"))
      (node (ref "U3") (pin "18") (pinfunction "PB0_18") (pintype "passive"))
    )
    (net (code "38") (name "Net-(U3-PB14)") (class "Default")
      (node (ref "R15") (pin "1") (pinfunction "1_1") (pintype "passive"))
      (node (ref "U3") (pin "27") (pinfunction "PB14_27") (pintype "passive"))
    )
    (net (code "39") (name "Net-(U6-OSCI)") (class "Default")
      (node (ref "U6") (pin "1") (pinfunction "OSCI_1") (pintype "passive"))
      (node (ref "X2") (pin "1") (pinfunction "1_1") (pintype "passive"))
    )
    (net (code "40") (name "Net-(U6-OSCO)") (class "Default")
      (node (ref "U6") (pin "2") (pinfunction "OSCO_2") (pintype "passive"))
      (node (ref "X2") (pin "2") (pinfunction "2_2") (pintype "passive"))
    )
    (net (code "41") (name "Net-(U6-VBAT)") (class "Default")
      (node (ref "C24") (pin "1") (pinfunction "1_1") (pintype "passive"))
      (node (ref "D5") (pin "1") (pinfunction "1_1") (pintype "passive"))
      (node (ref "U6") (pin "3") (pinfunction "VBAT_3") (pintype "passive"))
    )
    (net (code "42") (name "Net-(U7-SCLK)") (class "Default")
      (node (ref "R17") (pin "1") (pinfunction "1_1") (pintype "passive"))
      (node (ref "U7") (pin "1") (pinfunction "SCLK_1") (pintype "passive"))
    )
    (net (code "43") (name "Net-(U7-SIO)") (class "Default")
      (node (ref "R19") (pin "1") (pinfunction "1_1") (pintype "passive"))
      (node (ref "U7") (pin "3") (pinfunction "SIO_3") (pintype "passive"))
    )
    (net (code "44") (name "Net-(U7-~{CS})") (class "Default")
      (node (ref "R18") (pin "1") (pinfunction "1_1") (pintype "passive"))
      (node (ref "U7") (pin "2") (pinfunction "~{CS}_2") (pintype "passive"))
    )
    (net (code "45") (name "Net-(U7-~{OT})") (class "Default")
      (node (ref "R20") (pin "1") (pinfunction "1_1") (pintype "passive"))
      (node (ref "U7") (pin "5") (pinfunction "~{OT}_5") (pintype "passive"))
    )
    (net (code "46") (name "unconnected-(U3-OSC32_IN-Pad3)") (class "Default")
      (node (ref "U3") (pin "3") (pinfunction "OSC32_IN_3") (pintype "passive"))
    )
    (net (code "47") (name "unconnected-(U3-OSC32_OUT-Pad4)") (class "Default")
      (node (ref "U3") (pin "4") (pinfunction "OSC32_OUT_4") (pintype "passive"))
    )
    (net (code "48") (name "unconnected-(U3-PA0-WKUP-Pad10)") (class "Default")
      (node (ref "U3") (pin "10") (pinfunction "PA0-WKUP_10") (pintype "passive"))
    )
    (net (code "49") (name "unconnected-(U3-PA1-Pad11)") (class "Default")
      (node (ref "U3") (pin "11") (pinfunction "PA1_11") (pintype "passive"))
    )
    (net (code "50") (name "unconnected-(U3-PB3-Pad39)") (class "Default")
      (node (ref "U3") (pin "39") (pinfunction "PB3_39") (pintype "passive"))
    )
    (net (code "51") (name "unconnected-(U3-PB8-Pad45)") (class "Default")
      (node (ref "U3") (pin "45") (pinfunction "PB8_45") (pintype "passive"))
    )
    (net (code "52") (name "unconnected-(U3-PB9-Pad46)") (class "Default")
      (node (ref "U3") (pin "46") (pinfunction "PB9_46") (pintype "passive"))
    )
    (net (code "53") (name "unconnected-(U3-PB12-Pad25)") (class "Default")
      (node (ref "U3") (pin "25") (pinfunction "PB12_25") (pintype "passive"))
    )
    (net (code "54") (name "unconnected-(U3-PB13-Pad26)") (class "Default")
      (node (ref "U3") (pin "26") (pinfunction "PB13_26") (pintype "passive"))
    )
    (net (code "55") (name "unconnected-(U3-PB15-Pad28)") (class "Default")
      (node (ref "U3") (pin "28") (pinfunction "PB15_28") (pintype "passive"))
    )
    (net (code "56") (name "unconnected-(U3-PC13-Pad2)") (class "Default")
      (node (ref "U3") (pin "2") (pinfunction "PC13_2") (pintype "passive"))
    )
    (net (code "57") (name "unconnected-(U3-USART_CK-Pad29)") (class "Default")
      (node (ref "U3") (pin "29") (pinfunction "USART_CK_29") (pintype "passive"))
    )
    (net (code "58") (name "unconnected-(U3-USART_RX-Pad31)") (class "Default")
      (node (ref "U3") (pin "31") (pinfunction "USART_RX_31") (pintype "passive"))
    )
    (net (code "59") (name "unconnected-(U3-USART_TX-Pad30)") (class "Default")
      (node (ref "U3") (pin "30") (pinfunction "USART_TX_30") (pintype "passive"))
    )
    (net (code "60") (name "unconnected-(U3-VBAT-Pad1)") (class "Default")
      (node (ref "U3") (pin "1") (pinfunction "VBAT_1") (pintype "passive"))
    )
    (net (code "61") (name "unconnected-(U4-IO0-Pad25)") (class "Default")
      (node (ref "U4") (pin "25") (pinfunction "IO0_25") (pintype "passive"))
    )
    (net (code "62") (name "unconnected-(U4-IO2-Pad24)") (class "Default")
      (node (ref "U4") (pin "24") (pinfunction "IO2_24") (pintype "passive"))
    )
    (net (code "63") (name "unconnected-(U4-IO4-Pad26)") (class "Default")
      (node (ref "U4") (pin "26") (pinfunction "IO4_26") (pintype "passive"))
    )
    (net (code "64") (name "unconnected-(U4-IO5-Pad29)") (class "Default")
      (node (ref "U4") (pin "29") (pinfunction "IO5_29") (pintype "passive"))
    )
    (net (code "65") (name "unconnected-(U4-IO12-Pad14)") (class "Default")
      (node (ref "U4") (pin "14") (pinfunction "IO12_14") (pintype "passive"))
    )
    (net (code "66") (name "unconnected-(U4-IO13-Pad16)") (class "Default")
      (node (ref "U4") (pin "16") (pinfunction "IO13_16") (pintype "passive"))
    )
    (net (code "67") (name "unconnected-(U4-IO14-Pad13)") (class "Default")
      (node (ref "U4") (pin "13") (pinfunction "IO14_13") (pintype "passive"))
    )
    (net (code "68") (name "unconnected-(U4-IO15-Pad23)") (class "Default")
      (node (ref "U4") (pin "23") (pinfunction "IO15_23") (pintype "passive"))
    )
    (net (code "69") (name "unconnected-(U4-IO16-Pad27)") (class "Default")
      (node (ref "U4") (pin "27") (pinfunction "IO16_27") (pintype "passive"))
    )
    (net (code "70") (name "unconnected-(U4-IO17-Pad28)") (class "Default")
      (node (ref "U4") (pin "28") (pinfunction "IO17_28") (pintype "passive"))
    )
    (net (code "71") (name "unconnected-(U4-IO18-Pad30)") (class "Default")
      (node (ref "U4") (pin "30") (pinfunction "IO18_30") (pintype "passive"))
    )
    (net (code "72") (name "unconnected-(U4-IO19-Pad31)") (class "Default")
      (node (ref "U4") (pin "31") (pinfunction "IO19_31") (pintype "passive"))
    )
    (net (code "73") (name "unconnected-(U4-IO21-Pad33)") (class "Default")
      (node (ref "U4") (pin "33") (pinfunction "IO21_33") (pintype "passive"))
    )
    (net (code "74") (name "unconnected-(U4-IO22-Pad36)") (class "Default")
      (node (ref "U4") (pin "36") (pinfunction "IO22_36") (pintype "passive"))
    )
    (net (code "75") (name "unconnected-(U4-IO23-Pad37)") (class "Default")
      (node (ref "U4") (pin "37") (pinfunction "IO23_37") (pintype "passive"))
    )
    (net (code "76") (name "unconnected-(U4-IO25-Pad10)") (class "Default")
      (node (ref "U4") (pin "10") (pinfunction "IO25_10") (pintype "passive"))
    )
    (net (code "77") (name "unconnected-(U4-IO26-Pad11)") (class "Default")
      (node (ref "U4") (pin "11") (pinfunction "IO26_11") (pintype "passive"))
    )
    (net (code "78") (name "unconnected-(U4-IO27-Pad12)") (class "Default")
      (node (ref "U4") (pin "12") (pinfunction "IO27_12") (pintype "passive"))
    )
    (net (code "79") (name "unconnected-(U4-IO32-Pad8)") (class "Default")
      (node (ref "U4") (pin "8") (pinfunction "IO32_8") (pintype "passive"))
    )
    (net (code "80") (name "unconnected-(U4-IO33-Pad9)") (class "Default")
      (node (ref "U4") (pin "9") (pinfunction "IO33_9") (pintype "passive"))
    )
    (net (code "81") (name "unconnected-(U4-IO34-Pad6)") (class "Default")
      (node (ref "U4") (pin "6") (pinfunction "IO34_6") (pintype "passive"))
    )
    (net (code "82") (name "unconnected-(U4-IO35-Pad7)") (class "Default")
      (node (ref "U4") (pin "7") (pinfunction "IO35_7") (pintype "passive"))
    )
    (net (code "83") (name "unconnected-(U4-NC-Pad17)") (class "Default")
      (node (ref "U4") (pin "17") (pinfunction "NC_17") (pintype "passive+no_connect"))
    )
    (net (code "84") (name "unconnected-(U4-NC-Pad18)") (class "Default")
      (node (ref "U4") (pin "18") (pinfunction "NC_18") (pintype "passive+no_connect"))
    )
    (net (code "85") (name "unconnected-(U4-NC-Pad19)") (class "Default")
      (node (ref "U4") (pin "19") (pinfunction "NC_19") (pintype "passive+no_connect"))
    )
    (net (code "86") (name "unconnected-(U4-NC-Pad20)") (class "Default")
      (node (ref "U4") (pin "20") (pinfunction "NC_20") (pintype "passive+no_connect"))
    )
    (net (code "87") (name "unconnected-(U4-NC-Pad21)") (class "Default")
      (node (ref "U4") (pin "21") (pinfunction "NC_21") (pintype "passive+no_connect"))
    )
    (net (code "88") (name "unconnected-(U4-NC-Pad22)") (class "Default")
      (node (ref "U4") (pin "22") (pinfunction "NC_22") (pintype "passive+no_connect"))
    )
    (net (code "89") (name "unconnected-(U4-NC-Pad32)") (class "Default")
      (node (ref "U4") (pin "32") (pinfunction "NC_32") (pintype "passive+no_connect"))
    )
    (net (code "90") (name "unconnected-(U4-SENSOR_VN-Pad5)") (class "Default")
      (node (ref "U4") (pin "5") (pinfunction "SENSOR_VN_5") (pintype "passive"))
    )
    (net (code "91") (name "unconnected-(U4-SENSOR_VP-Pad4)") (class "Default")
      (node (ref "U4") (pin "4") (pinfunction "SENSOR_VP_4") (pintype "passive"))
    )
    (net (code "92") (name "unconnected-(U6-FT{slash}OUT-Pad7)") (class "Default")
      (node (ref "U6") (pin "7") (pinfunction "FT/OUT_7") (pintype "passive"))
    )
    (net (code "93") (name "unconnected-(U7-NC-Pad7)") (class "Default")
      (node (ref "U7") (pin "7") (pinfunction "NC_7") (pintype "passive+no_connect"))
    )
    (net (code "94") (name "unconnected-(U7-~{ALERT}-Pad6)") (class "Default")
      (node (ref "U7") (pin "6") (pinfunction "~{ALERT}_6") (pintype "passive"))
    )
  )
)
